# charge_drv.net
KiCad netlist of a schematic drawn in Altium Designer
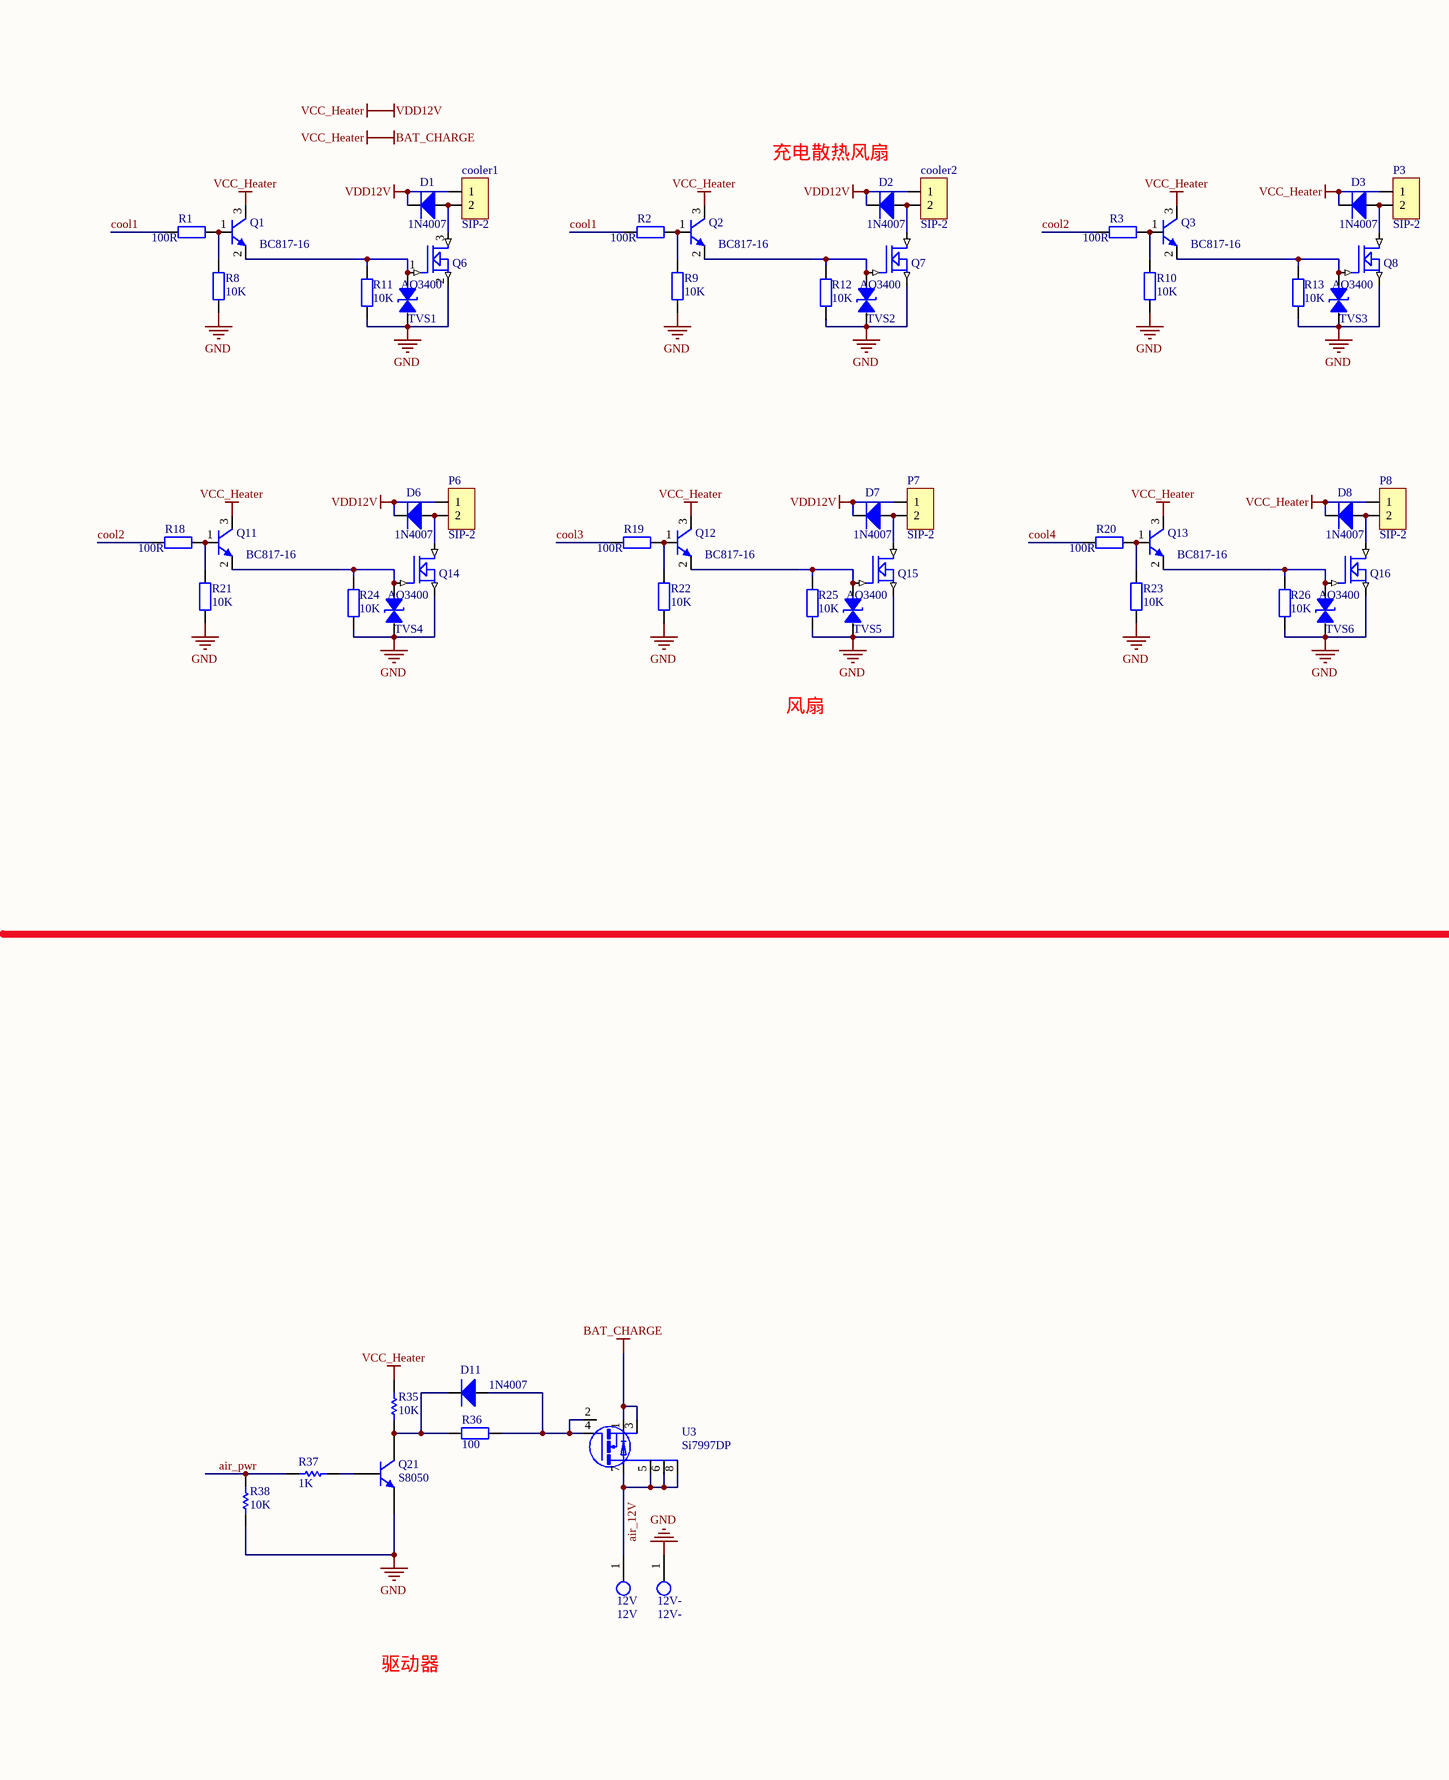
[diagram p0: charge_drv.SchDoc, left]
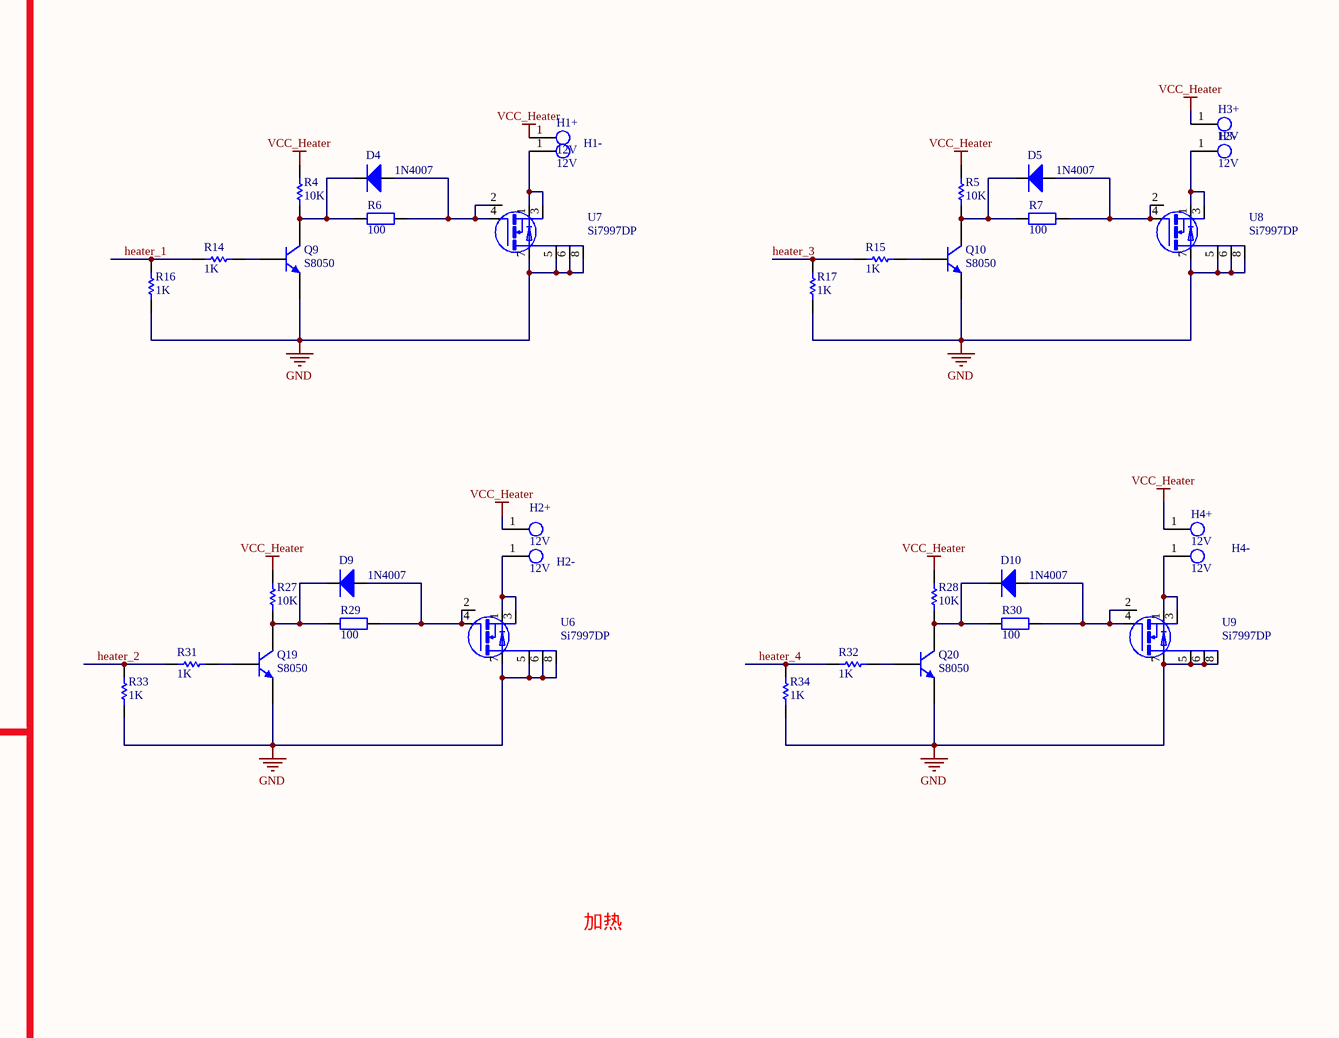
[diagram p1: charge_drv.SchDoc, right]

(export (version "E")
  (design (tool "Eeschema 10.0.6"))
  (components
    (comp (ref "12V") (value "12V") (footprint "FIX-4.5") (libsource (lib "Schlib_20110825") (part "TP")))
    (comp (ref "12V-") (value "12V-") (footprint "FIX-4.5") (libsource (lib "Schlib_20110825") (part "TP")))
    (comp (ref "cooler1")
      (value "SIP-2")
      (footprint "SIP-2A")
      (description "XH2.54 2P 立贴")
      (libsource (lib "XiaoyI") (part "SIP-2"))
    )
    (comp (ref "cooler2")
      (value "SIP-2")
      (footprint "SIP-2A")
      (description "XH2.54 2P 立贴")
      (libsource (lib "XiaoyI") (part "SIP-2"))
    )
    (comp (ref "D1")
      (value "1N4007")
      (footprint "DO-214-AC")
      (description "贴片二极管")
      (libsource (lib "XiaoyI") (part "DIODE2"))
    )
    (comp (ref "D2")
      (value "1N4007")
      (footprint "DO-214-AC")
      (description "贴片二极管")
      (libsource (lib "XiaoyI") (part "DIODE2"))
    )
    (comp (ref "D3")
      (value "1N4007")
      (footprint "DO-214-AC")
      (description "贴片二极管")
      (libsource (lib "XiaoyI") (part "DIODE2"))
    )
    (comp (ref "D4")
      (value "1N4007")
      (footprint "DO-214-AC")
      (description "贴片二极管")
      (libsource (lib "XiaoyI") (part "DIODE2"))
    )
    (comp (ref "D5")
      (value "1N4007")
      (footprint "DO-214-AC")
      (description "贴片二极管")
      (libsource (lib "XiaoyI") (part "DIODE2"))
    )
    (comp (ref "D6")
      (value "1N4007")
      (footprint "DO-214-AC")
      (description "贴片二极管")
      (libsource (lib "XiaoyI") (part "DIODE2"))
    )
    (comp (ref "D7")
      (value "1N4007")
      (footprint "DO-214-AC")
      (description "贴片二极管")
      (libsource (lib "XiaoyI") (part "DIODE2"))
    )
    (comp (ref "D8")
      (value "1N4007")
      (footprint "DO-214-AC")
      (description "贴片二极管")
      (libsource (lib "XiaoyI") (part "DIODE2"))
    )
    (comp (ref "D9")
      (value "1N4007")
      (footprint "DO-214-AC")
      (description "贴片二极管")
      (libsource (lib "XiaoyI") (part "DIODE2"))
    )
    (comp (ref "D10")
      (value "1N4007")
      (footprint "DO-214-AC")
      (description "贴片二极管")
      (libsource (lib "XiaoyI") (part "DIODE2"))
    )
    (comp (ref "D11")
      (value "1N4007")
      (footprint "DO-214-AC")
      (description "贴片二极管")
      (libsource (lib "XiaoyI") (part "DIODE2"))
    )
    (comp (ref "H1+") (value "12V") (footprint "FIX-4.5") (libsource (lib "Schlib_20110825") (part "TP")))
    (comp (ref "H1-") (value "12V") (footprint "FIX-4.5") (libsource (lib "Schlib_20110825") (part "TP")))
    (comp (ref "H2+") (value "12V") (footprint "FIX-4.5") (libsource (lib "Schlib_20110825") (part "TP")))
    (comp (ref "H2-") (value "12V") (footprint "FIX-4.5") (libsource (lib "Schlib_20110825") (part "TP")))
    (comp (ref "H3+") (value "12V") (footprint "FIX-4.5") (libsource (lib "Schlib_20110825") (part "TP")))
    (comp (ref "H3-") (value "12V") (footprint "FIX-4.5") (libsource (lib "Schlib_20110825") (part "TP")))
    (comp (ref "H4+") (value "12V") (footprint "FIX-4.5") (libsource (lib "Schlib_20110825") (part "TP")))
    (comp (ref "H4-") (value "12V") (footprint "FIX-4.5") (libsource (lib "Schlib_20110825") (part "TP")))
    (comp (ref "P3")
      (value "SIP-2")
      (footprint "SIP-2A")
      (description "XH2.54 2P 立贴")
      (libsource (lib "XiaoyI") (part "SIP-2"))
    )
    (comp (ref "P6")
      (value "SIP-2")
      (footprint "SIP-2A")
      (description "XH2.54 2P 立贴")
      (libsource (lib "XiaoyI") (part "SIP-2"))
    )
    (comp (ref "P7")
      (value "SIP-2")
      (footprint "SIP-2A")
      (description "XH2.54 2P 立贴")
      (libsource (lib "XiaoyI") (part "SIP-2"))
    )
    (comp (ref "P8")
      (value "SIP-2")
      (footprint "SIP-2A")
      (description "XH2.54 2P 立贴")
      (libsource (lib "XiaoyI") (part "SIP-2"))
    )
    (comp (ref "Q1")
      (value "BC817-16")
      (footprint "SOT23-3")
      (description "三极管")
      (libsource (lib "XiaoyI") (part "NPN-1"))
    )
    (comp (ref "Q2")
      (value "BC817-16")
      (footprint "SOT23-3")
      (description "三极管")
      (libsource (lib "XiaoyI") (part "NPN-1"))
    )
    (comp (ref "Q3")
      (value "BC817-16")
      (footprint "SOT23-3")
      (description "三极管")
      (libsource (lib "XiaoyI") (part "NPN-1"))
    )
    (comp (ref "Q6")
      (value "AO3400")
      (footprint "SOT23-3")
      (description "MOSFET N")
      (libsource (lib "XiaoyI") (part "MOSFET N"))
    )
    (comp (ref "Q7")
      (value "AO3400")
      (footprint "SOT23-3")
      (description "MOSFET N")
      (libsource (lib "") (part "MOSFET N_1"))
    )
    (comp (ref "Q8")
      (value "AO3400")
      (footprint "SOT23-3")
      (description "MOSFET N")
      (libsource (lib "") (part "MOSFET N_1"))
    )
    (comp (ref "Q9")
      (value "S8050")
      (footprint "SOT23-3")
      (description "NPN Bipolar Transistor")
      (fields (field (name "PUBLISHER") "Altium Limited"))
      (libsource (lib "Miscellaneous Devices") (part "NPN"))
    )
    (comp (ref "Q10")
      (value "S8050")
      (footprint "SOT23-3")
      (description "NPN Bipolar Transistor")
      (fields (field (name "PUBLISHER") "Altium Limited"))
      (libsource (lib "Miscellaneous Devices") (part "NPN"))
    )
    (comp (ref "Q11")
      (value "BC817-16")
      (footprint "SOT23-3")
      (description "三极管")
      (libsource (lib "XiaoyI") (part "NPN-1"))
    )
    (comp (ref "Q12")
      (value "BC817-16")
      (footprint "SOT23-3")
      (description "三极管")
      (libsource (lib "XiaoyI") (part "NPN-1"))
    )
    (comp (ref "Q13")
      (value "BC817-16")
      (footprint "SOT23-3")
      (description "三极管")
      (libsource (lib "XiaoyI") (part "NPN-1"))
    )
    (comp (ref "Q14")
      (value "AO3400")
      (footprint "SOT23-3")
      (description "MOSFET N")
      (libsource (lib "") (part "MOSFET N_1"))
    )
    (comp (ref "Q15")
      (value "AO3400")
      (footprint "SOT23-3")
      (description "MOSFET N")
      (libsource (lib "") (part "MOSFET N_1"))
    )
    (comp (ref "Q16")
      (value "AO3400")
      (footprint "SOT23-3")
      (description "MOSFET N")
      (libsource (lib "") (part "MOSFET N_1"))
    )
    (comp (ref "Q19")
      (value "S8050")
      (footprint "SOT23-3")
      (description "NPN Bipolar Transistor")
      (fields (field (name "PUBLISHER") "Altium Limited"))
      (libsource (lib "Miscellaneous Devices") (part "NPN"))
    )
    (comp (ref "Q20")
      (value "S8050")
      (footprint "SOT23-3")
      (description "NPN Bipolar Transistor")
      (fields (field (name "PUBLISHER") "Altium Limited"))
      (libsource (lib "Miscellaneous Devices") (part "NPN"))
    )
    (comp (ref "Q21")
      (value "S8050")
      (footprint "SOT23-3")
      (description "NPN Bipolar Transistor")
      (fields (field (name "PUBLISHER") "Altium Limited"))
      (libsource (lib "Miscellaneous Devices") (part "NPN"))
    )
    (comp (ref "R1")
      (value "100R")
      (footprint "0603R")
      (description "贴片电阻 5%")
      (libsource (lib "") (part "RES-SOP_3"))
    )
    (comp (ref "R2")
      (value "100R")
      (footprint "0603R")
      (description "贴片电阻 5%")
      (libsource (lib "") (part "RES-SOP_3"))
    )
    (comp (ref "R3")
      (value "100R")
      (footprint "0603R")
      (description "贴片电阻 5%")
      (libsource (lib "") (part "RES-SOP_3"))
    )
    (comp (ref "R4")
      (value "10K")
      (footprint "0603R")
      (description "Resistor")
      (fields (field (name "PUBLISHER") "Altium Limited"))
      (libsource (lib "Miscellaneous Devices") (part "Res1"))
    )
    (comp (ref "R5")
      (value "10K")
      (footprint "0603R")
      (description "Resistor")
      (fields (field (name "PUBLISHER") "Altium Limited"))
      (libsource (lib "Miscellaneous Devices") (part "Res1"))
    )
    (comp (ref "R6")
      (value "100")
      (footprint "0603R")
      (description "贴片电阻 5%")
      (libsource (lib "") (part "RES-SOP_1"))
    )
    (comp (ref "R7")
      (value "100")
      (footprint "0603R")
      (description "贴片电阻 5%")
      (libsource (lib "") (part "RES-SOP_1"))
    )
    (comp (ref "R8")
      (value "10K")
      (footprint "0603R")
      (description "贴片电阻 5%")
      (libsource (lib "") (part "RES-SOP_2"))
    )
    (comp (ref "R9")
      (value "10K")
      (footprint "0603R")
      (description "贴片电阻 5%")
      (libsource (lib "") (part "RES-SOP_2"))
    )
    (comp (ref "R10")
      (value "10K")
      (footprint "0603R")
      (description "贴片电阻 5%")
      (libsource (lib "") (part "RES-SOP_2"))
    )
    (comp (ref "R11")
      (value "10K")
      (footprint "0603R")
      (description "贴片电阻 5%")
      (libsource (lib "XiaoyI") (part "RES-SOP"))
    )
    (comp (ref "R12")
      (value "10K")
      (footprint "0603R")
      (description "贴片电阻 5%")
      (libsource (lib "XiaoyI") (part "RES-SOP"))
    )
    (comp (ref "R13")
      (value "10K")
      (footprint "0603R")
      (description "贴片电阻 5%")
      (libsource (lib "XiaoyI") (part "RES-SOP"))
    )
    (comp (ref "R14")
      (value "1K")
      (footprint "0603R")
      (description "Resistor")
      (fields (field (name "PUBLISHER") "Altium Limited"))
      (libsource (lib "Miscellaneous Devices") (part "Res1"))
    )
    (comp (ref "R15")
      (value "1K")
      (footprint "0603R")
      (description "Resistor")
      (fields (field (name "PUBLISHER") "Altium Limited"))
      (libsource (lib "Miscellaneous Devices") (part "Res1"))
    )
    (comp (ref "R16")
      (value "1K")
      (footprint "0603R")
      (description "Resistor")
      (fields (field (name "PUBLISHER") "Altium Limited"))
      (libsource (lib "Miscellaneous Devices") (part "Res1"))
    )
    (comp (ref "R17")
      (value "1K")
      (footprint "0603R")
      (description "Resistor")
      (fields (field (name "PUBLISHER") "Altium Limited"))
      (libsource (lib "Miscellaneous Devices") (part "Res1"))
    )
    (comp (ref "R18")
      (value "100R")
      (footprint "0603R")
      (description "贴片电阻 5%")
      (libsource (lib "") (part "RES-SOP_3"))
    )
    (comp (ref "R19")
      (value "100R")
      (footprint "0603R")
      (description "贴片电阻 5%")
      (libsource (lib "") (part "RES-SOP_3"))
    )
    (comp (ref "R20")
      (value "100R")
      (footprint "0603R")
      (description "贴片电阻 5%")
      (libsource (lib "") (part "RES-SOP_3"))
    )
    (comp (ref "R21")
      (value "10K")
      (footprint "0603R")
      (description "贴片电阻 5%")
      (libsource (lib "") (part "RES-SOP_2"))
    )
    (comp (ref "R22")
      (value "10K")
      (footprint "0603R")
      (description "贴片电阻 5%")
      (libsource (lib "") (part "RES-SOP_2"))
    )
    (comp (ref "R23")
      (value "10K")
      (footprint "0603R")
      (description "贴片电阻 5%")
      (libsource (lib "") (part "RES-SOP_2"))
    )
    (comp (ref "R24")
      (value "10K")
      (footprint "0603R")
      (description "贴片电阻 5%")
      (libsource (lib "XiaoyI") (part "RES-SOP"))
    )
    (comp (ref "R25")
      (value "10K")
      (footprint "0603R")
      (description "贴片电阻 5%")
      (libsource (lib "XiaoyI") (part "RES-SOP"))
    )
    (comp (ref "R26")
      (value "10K")
      (footprint "0603R")
      (description "贴片电阻 5%")
      (libsource (lib "XiaoyI") (part "RES-SOP"))
    )
    (comp (ref "R27")
      (value "10K")
      (footprint "0603R")
      (description "Resistor")
      (fields (field (name "PUBLISHER") "Altium Limited"))
      (libsource (lib "Miscellaneous Devices") (part "Res1"))
    )
    (comp (ref "R28")
      (value "10K")
      (footprint "0603R")
      (description "Resistor")
      (fields (field (name "PUBLISHER") "Altium Limited"))
      (libsource (lib "Miscellaneous Devices") (part "Res1"))
    )
    (comp (ref "R29")
      (value "100")
      (footprint "0603R")
      (description "贴片电阻 5%")
      (libsource (lib "") (part "RES-SOP_1"))
    )
    (comp (ref "R30")
      (value "100")
      (footprint "0603R")
      (description "贴片电阻 5%")
      (libsource (lib "") (part "RES-SOP_1"))
    )
    (comp (ref "R31")
      (value "1K")
      (footprint "0603R")
      (description "Resistor")
      (fields (field (name "PUBLISHER") "Altium Limited"))
      (libsource (lib "Miscellaneous Devices") (part "Res1"))
    )
    (comp (ref "R32")
      (value "1K")
      (footprint "0603R")
      (description "Resistor")
      (fields (field (name "PUBLISHER") "Altium Limited"))
      (libsource (lib "Miscellaneous Devices") (part "Res1"))
    )
    (comp (ref "R33")
      (value "1K")
      (footprint "0603R")
      (description "Resistor")
      (fields (field (name "PUBLISHER") "Altium Limited"))
      (libsource (lib "Miscellaneous Devices") (part "Res1"))
    )
    (comp (ref "R34")
      (value "1K")
      (footprint "0603R")
      (description "Resistor")
      (fields (field (name "PUBLISHER") "Altium Limited"))
      (libsource (lib "Miscellaneous Devices") (part "Res1"))
    )
    (comp (ref "R35")
      (value "10K")
      (footprint "0603R")
      (description "Resistor")
      (fields (field (name "PUBLISHER") "Altium Limited"))
      (libsource (lib "Miscellaneous Devices") (part "Res1"))
    )
    (comp (ref "R36")
      (value "100")
      (footprint "0603R")
      (description "贴片电阻 5%")
      (libsource (lib "") (part "RES-SOP_1"))
    )
    (comp (ref "R37")
      (value "1K")
      (footprint "0603R")
      (description "Resistor")
      (fields (field (name "PUBLISHER") "Altium Limited"))
      (libsource (lib "Miscellaneous Devices") (part "Res1"))
    )
    (comp (ref "R38")
      (value "10K")
      (footprint "0603R")
      (description "Resistor")
      (fields (field (name "PUBLISHER") "Altium Limited"))
      (libsource (lib "Miscellaneous Devices") (part "Res1"))
    )
    (comp (ref "TVS1")
      (value "ESD5Z5.0CT1G")
      (footprint "SOD-523")
      (description "TVS")
      (libsource (lib "XiaoyI") (part "TVS-1"))
    )
    (comp (ref "TVS2")
      (value "ESD5Z5.0CT1G")
      (footprint "SOD-523")
      (description "TVS")
      (libsource (lib "XiaoyI") (part "TVS-1"))
    )
    (comp (ref "TVS3")
      (value "ESD5Z5.0CT1G")
      (footprint "SOD-523")
      (description "TVS")
      (libsource (lib "XiaoyI") (part "TVS-1"))
    )
    (comp (ref "TVS4")
      (value "ESD5Z5.0CT1G")
      (footprint "SOD-523")
      (description "TVS")
      (libsource (lib "XiaoyI") (part "TVS-1"))
    )
    (comp (ref "TVS5")
      (value "ESD5Z5.0CT1G")
      (footprint "SOD-523")
      (description "TVS")
      (libsource (lib "XiaoyI") (part "TVS-1"))
    )
    (comp (ref "TVS6")
      (value "ESD5Z5.0CT1G")
      (footprint "SOD-523")
      (description "TVS")
      (libsource (lib "XiaoyI") (part "TVS-1"))
    )
    (comp (ref "U3")
      (value "Si7997DP")
      (footprint "PowerPAK SO-8")
      (description "Sia430DJ")
      (libsource (lib "Schlib_20110825") (part "Si7997DP"))
    )
    (comp (ref "U6")
      (value "Si7997DP")
      (footprint "PowerPAK SO-8")
      (description "Sia430DJ")
      (libsource (lib "Schlib_20110825") (part "Si7997DP"))
    )
    (comp (ref "U7")
      (value "Si7997DP")
      (footprint "PowerPAK SO-8")
      (description "Sia430DJ")
      (libsource (lib "Schlib_20110825") (part "Si7997DP"))
    )
    (comp (ref "U8")
      (value "Si7997DP")
      (footprint "PowerPAK SO-8")
      (description "Sia430DJ")
      (libsource (lib "Schlib_20110825") (part "Si7997DP"))
    )
    (comp (ref "U9")
      (value "Si7997DP")
      (footprint "PowerPAK SO-8")
      (description "Sia430DJ")
      (libsource (lib "Schlib_20110825") (part "Si7997DP"))
    )
  )
  (nets
    (net (code "1") (name "/air_12V") (class "Default")
      (node (ref "12V") (pin "1") (pintype "passive"))
      (node (ref "U3") (pin "5") (pinfunction "D_5") (pintype "passive"))
      (node (ref "U3") (pin "6") (pinfunction "D_6") (pintype "passive"))
      (node (ref "U3") (pin "7") (pinfunction "D_7") (pintype "passive"))
      (node (ref "U3") (pin "8") (pinfunction "D_8") (pintype "passive"))
    )
    (net (code "2") (name "/air_pwr") (class "Default")
      (node (ref "R37") (pin "2") (pinfunction "2_2") (pintype "passive"))
      (node (ref "R38") (pin "1") (pinfunction "1_1") (pintype "passive"))
    )
    (net (code "3") (name "/cool1") (class "Default")
      (node (ref "R1") (pin "2") (pinfunction "2_2") (pintype "passive"))
      (node (ref "R2") (pin "2") (pinfunction "2_2") (pintype "passive"))
    )
    (net (code "4") (name "/cool2") (class "Default")
      (node (ref "R18") (pin "2") (pinfunction "2_2") (pintype "passive"))
      (node (ref "R3") (pin "2") (pinfunction "2_2") (pintype "passive"))
    )
    (net (code "5") (name "/cool3") (class "Default")
      (node (ref "R19") (pin "2") (pinfunction "2_2") (pintype "passive"))
    )
    (net (code "6") (name "/cool4") (class "Default")
      (node (ref "R20") (pin "2") (pinfunction "2_2") (pintype "passive"))
    )
    (net (code "7") (name "/heater_1") (class "Default")
      (node (ref "R14") (pin "2") (pinfunction "2_2") (pintype "passive"))
      (node (ref "R16") (pin "1") (pinfunction "1_1") (pintype "passive"))
    )
    (net (code "8") (name "/heater_2") (class "Default")
      (node (ref "R31") (pin "2") (pinfunction "2_2") (pintype "passive"))
      (node (ref "R33") (pin "1") (pinfunction "1_1") (pintype "passive"))
    )
    (net (code "9") (name "/heater_3") (class "Default")
      (node (ref "R15") (pin "2") (pinfunction "2_2") (pintype "passive"))
      (node (ref "R17") (pin "1") (pinfunction "1_1") (pintype "passive"))
    )
    (net (code "10") (name "/heater_4") (class "Default")
      (node (ref "R32") (pin "2") (pinfunction "2_2") (pintype "passive"))
      (node (ref "R34") (pin "1") (pinfunction "1_1") (pintype "passive"))
    )
    (net (code "11") (name "BAT_CHARGE") (class "Default")
      (node (ref "D1") (pin "2") (pinfunction "K_2") (pintype "passive"))
      (node (ref "D2") (pin "2") (pinfunction "K_2") (pintype "passive"))
      (node (ref "D3") (pin "2") (pinfunction "K_2") (pintype "passive"))
      (node (ref "D6") (pin "2") (pinfunction "K_2") (pintype "passive"))
      (node (ref "D7") (pin "2") (pinfunction "K_2") (pintype "passive"))
      (node (ref "D8") (pin "2") (pinfunction "K_2") (pintype "passive"))
      (node (ref "H1+") (pin "1") (pintype "passive"))
      (node (ref "H2+") (pin "1") (pintype "passive"))
      (node (ref "H3+") (pin "1") (pintype "passive"))
      (node (ref "H4+") (pin "1") (pintype "passive"))
      (node (ref "P3") (pin "1") (pinfunction "1_1") (pintype "passive"))
      (node (ref "P6") (pin "1") (pinfunction "1_1") (pintype "passive"))
      (node (ref "P7") (pin "1") (pinfunction "1_1") (pintype "passive"))
      (node (ref "P8") (pin "1") (pinfunction "1_1") (pintype "passive"))
      (node (ref "Q1") (pin "3") (pinfunction "C_3") (pintype "passive"))
      (node (ref "Q11") (pin "3") (pinfunction "C_3") (pintype "passive"))
      (node (ref "Q12") (pin "3") (pinfunction "C_3") (pintype "passive"))
      (node (ref "Q13") (pin "3") (pinfunction "C_3") (pintype "passive"))
      (node (ref "Q2") (pin "3") (pinfunction "C_3") (pintype "passive"))
      (node (ref "Q3") (pin "3") (pinfunction "C_3") (pintype "passive"))
      (node (ref "R27") (pin "2") (pinfunction "2_2") (pintype "passive"))
      (node (ref "R28") (pin "2") (pinfunction "2_2") (pintype "passive"))
      (node (ref "R35") (pin "2") (pinfunction "2_2") (pintype "passive"))
      (node (ref "R4") (pin "2") (pinfunction "2_2") (pintype "passive"))
      (node (ref "R5") (pin "2") (pinfunction "2_2") (pintype "passive"))
      (node (ref "U3") (pin "1") (pinfunction "S_1") (pintype "passive"))
      (node (ref "U3") (pin "3") (pinfunction "S_3") (pintype "passive"))
      (node (ref "cooler1") (pin "1") (pinfunction "1_1") (pintype "passive"))
      (node (ref "cooler2") (pin "1") (pinfunction "1_1") (pintype "passive"))
    )
    (net (code "12") (name "GND") (class "Default")
      (node (ref "12V-") (pin "1") (pintype "passive"))
      (node (ref "Q10") (pin "2") (pinfunction "E_2") (pintype "passive"))
      (node (ref "Q14") (pin "2") (pinfunction "S_2") (pintype "output"))
      (node (ref "Q15") (pin "2") (pinfunction "S_2") (pintype "output"))
      (node (ref "Q16") (pin "2") (pinfunction "S_2") (pintype "output"))
      (node (ref "Q19") (pin "2") (pinfunction "E_2") (pintype "passive"))
      (node (ref "Q20") (pin "2") (pinfunction "E_2") (pintype "passive"))
      (node (ref "Q21") (pin "2") (pinfunction "E_2") (pintype "passive"))
      (node (ref "Q6") (pin "2") (pinfunction "S_2") (pintype "output"))
      (node (ref "Q7") (pin "2") (pinfunction "S_2") (pintype "output"))
      (node (ref "Q8") (pin "2") (pinfunction "S_2") (pintype "output"))
      (node (ref "Q9") (pin "2") (pinfunction "E_2") (pintype "passive"))
      (node (ref "R10") (pin "1") (pinfunction "1_1") (pintype "passive"))
      (node (ref "R11") (pin "2") (pinfunction "2_2") (pintype "passive"))
      (node (ref "R12") (pin "2") (pinfunction "2_2") (pintype "passive"))
      (node (ref "R13") (pin "2") (pinfunction "2_2") (pintype "passive"))
      (node (ref "R16") (pin "2") (pinfunction "2_2") (pintype "passive"))
      (node (ref "R17") (pin "2") (pinfunction "2_2") (pintype "passive"))
      (node (ref "R21") (pin "1") (pinfunction "1_1") (pintype "passive"))
      (node (ref "R22") (pin "1") (pinfunction "1_1") (pintype "passive"))
      (node (ref "R23") (pin "1") (pinfunction "1_1") (pintype "passive"))
      (node (ref "R24") (pin "2") (pinfunction "2_2") (pintype "passive"))
      (node (ref "R25") (pin "2") (pinfunction "2_2") (pintype "passive"))
      (node (ref "R26") (pin "2") (pinfunction "2_2") (pintype "passive"))
      (node (ref "R33") (pin "2") (pinfunction "2_2") (pintype "passive"))
      (node (ref "R34") (pin "2") (pinfunction "2_2") (pintype "passive"))
      (node (ref "R38") (pin "2") (pinfunction "2_2") (pintype "passive"))
      (node (ref "R8") (pin "1") (pinfunction "1_1") (pintype "passive"))
      (node (ref "R9") (pin "1") (pinfunction "1_1") (pintype "passive"))
      (node (ref "TVS1") (pin "1") (pinfunction "A_1") (pintype "passive"))
      (node (ref "TVS2") (pin "1") (pinfunction "A_1") (pintype "passive"))
      (node (ref "TVS3") (pin "1") (pinfunction "A_1") (pintype "passive"))
      (node (ref "TVS4") (pin "1") (pinfunction "A_1") (pintype "passive"))
      (node (ref "TVS5") (pin "1") (pinfunction "A_1") (pintype "passive"))
      (node (ref "TVS6") (pin "1") (pinfunction "A_1") (pintype "passive"))
      (node (ref "U6") (pin "5") (pinfunction "D_5") (pintype "passive"))
      (node (ref "U6") (pin "6") (pinfunction "D_6") (pintype "passive"))
      (node (ref "U6") (pin "7") (pinfunction "D_7") (pintype "passive"))
      (node (ref "U6") (pin "8") (pinfunction "D_8") (pintype "passive"))
      (node (ref "U7") (pin "5") (pinfunction "D_5") (pintype "passive"))
      (node (ref "U7") (pin "6") (pinfunction "D_6") (pintype "passive"))
      (node (ref "U7") (pin "7") (pinfunction "D_7") (pintype "passive"))
      (node (ref "U7") (pin "8") (pinfunction "D_8") (pintype "passive"))
      (node (ref "U8") (pin "5") (pinfunction "D_5") (pintype "passive"))
      (node (ref "U8") (pin "6") (pinfunction "D_6") (pintype "passive"))
      (node (ref "U8") (pin "7") (pinfunction "D_7") (pintype "passive"))
      (node (ref "U8") (pin "8") (pinfunction "D_8") (pintype "passive"))
      (node (ref "U9") (pin "5") (pinfunction "D_5") (pintype "passive"))
      (node (ref "U9") (pin "6") (pinfunction "D_6") (pintype "passive"))
      (node (ref "U9") (pin "7") (pinfunction "D_7") (pintype "passive"))
      (node (ref "U9") (pin "8") (pinfunction "D_8") (pintype "passive"))
    )
    (net (code "13") (name "Net-(D1-A)") (class "Default")
      (node (ref "D1") (pin "1") (pinfunction "A_1") (pintype "passive"))
      (node (ref "Q6") (pin "3") (pinfunction "D_3") (pintype "input"))
      (node (ref "cooler1") (pin "2") (pinfunction "2_2") (pintype "passive"))
    )
    (net (code "14") (name "Net-(D2-A)") (class "Default")
      (node (ref "D2") (pin "1") (pinfunction "A_1") (pintype "passive"))
      (node (ref "Q7") (pin "3") (pinfunction "D_3") (pintype "input"))
      (node (ref "cooler2") (pin "2") (pinfunction "2_2") (pintype "passive"))
    )
    (net (code "15") (name "Net-(D3-A)") (class "Default")
      (node (ref "D3") (pin "1") (pinfunction "A_1") (pintype "passive"))
      (node (ref "P3") (pin "2") (pinfunction "2_2") (pintype "passive"))
      (node (ref "Q8") (pin "3") (pinfunction "D_3") (pintype "input"))
    )
    (net (code "16") (name "Net-(D4-A)") (class "Default")
      (node (ref "D4") (pin "1") (pinfunction "A_1") (pintype "passive"))
      (node (ref "R6") (pin "2") (pinfunction "2_2") (pintype "passive"))
      (node (ref "U7") (pin "2") (pinfunction "G_2") (pintype "passive"))
      (node (ref "U7") (pin "4") (pinfunction "G_4") (pintype "passive"))
    )
    (net (code "17") (name "Net-(D4-K)") (class "Default")
      (node (ref "D4") (pin "2") (pinfunction "K_2") (pintype "passive"))
      (node (ref "Q9") (pin "3") (pinfunction "C_3") (pintype "passive"))
      (node (ref "R4") (pin "1") (pinfunction "1_1") (pintype "passive"))
      (node (ref "R6") (pin "1") (pinfunction "1_1") (pintype "passive"))
    )
    (net (code "18") (name "Net-(D5-A)") (class "Default")
      (node (ref "D5") (pin "1") (pinfunction "A_1") (pintype "passive"))
      (node (ref "R7") (pin "2") (pinfunction "2_2") (pintype "passive"))
      (node (ref "U8") (pin "2") (pinfunction "G_2") (pintype "passive"))
      (node (ref "U8") (pin "4") (pinfunction "G_4") (pintype "passive"))
    )
    (net (code "19") (name "Net-(D5-K)") (class "Default")
      (node (ref "D5") (pin "2") (pinfunction "K_2") (pintype "passive"))
      (node (ref "Q10") (pin "3") (pinfunction "C_3") (pintype "passive"))
      (node (ref "R5") (pin "1") (pinfunction "1_1") (pintype "passive"))
      (node (ref "R7") (pin "1") (pinfunction "1_1") (pintype "passive"))
    )
    (net (code "20") (name "Net-(D6-A)") (class "Default")
      (node (ref "D6") (pin "1") (pinfunction "A_1") (pintype "passive"))
      (node (ref "P6") (pin "2") (pinfunction "2_2") (pintype "passive"))
      (node (ref "Q14") (pin "3") (pinfunction "D_3") (pintype "input"))
    )
    (net (code "21") (name "Net-(D7-A)") (class "Default")
      (node (ref "D7") (pin "1") (pinfunction "A_1") (pintype "passive"))
      (node (ref "P7") (pin "2") (pinfunction "2_2") (pintype "passive"))
      (node (ref "Q15") (pin "3") (pinfunction "D_3") (pintype "input"))
    )
    (net (code "22") (name "Net-(D8-A)") (class "Default")
      (node (ref "D8") (pin "1") (pinfunction "A_1") (pintype "passive"))
      (node (ref "P8") (pin "2") (pinfunction "2_2") (pintype "passive"))
      (node (ref "Q16") (pin "3") (pinfunction "D_3") (pintype "input"))
    )
    (net (code "23") (name "Net-(D9-A)") (class "Default")
      (node (ref "D9") (pin "1") (pinfunction "A_1") (pintype "passive"))
      (node (ref "R29") (pin "2") (pinfunction "2_2") (pintype "passive"))
      (node (ref "U6") (pin "2") (pinfunction "G_2") (pintype "passive"))
      (node (ref "U6") (pin "4") (pinfunction "G_4") (pintype "passive"))
    )
    (net (code "24") (name "Net-(D9-K)") (class "Default")
      (node (ref "D9") (pin "2") (pinfunction "K_2") (pintype "passive"))
      (node (ref "Q19") (pin "3") (pinfunction "C_3") (pintype "passive"))
      (node (ref "R27") (pin "1") (pinfunction "1_1") (pintype "passive"))
      (node (ref "R29") (pin "1") (pinfunction "1_1") (pintype "passive"))
    )
    (net (code "25") (name "Net-(D10-A)") (class "Default")
      (node (ref "D10") (pin "1") (pinfunction "A_1") (pintype "passive"))
      (node (ref "R30") (pin "2") (pinfunction "2_2") (pintype "passive"))
      (node (ref "U9") (pin "2") (pinfunction "G_2") (pintype "passive"))
      (node (ref "U9") (pin "4") (pinfunction "G_4") (pintype "passive"))
    )
    (net (code "26") (name "Net-(D10-K)") (class "Default")
      (node (ref "D10") (pin "2") (pinfunction "K_2") (pintype "passive"))
      (node (ref "Q20") (pin "3") (pinfunction "C_3") (pintype "passive"))
      (node (ref "R28") (pin "1") (pinfunction "1_1") (pintype "passive"))
      (node (ref "R30") (pin "1") (pinfunction "1_1") (pintype "passive"))
    )
    (net (code "27") (name "Net-(D11-A)") (class "Default")
      (node (ref "D11") (pin "1") (pinfunction "A_1") (pintype "passive"))
      (node (ref "R36") (pin "2") (pinfunction "2_2") (pintype "passive"))
      (node (ref "U3") (pin "2") (pinfunction "G_2") (pintype "passive"))
      (node (ref "U3") (pin "4") (pinfunction "G_4") (pintype "passive"))
    )
    (net (code "28") (name "Net-(D11-K)") (class "Default")
      (node (ref "D11") (pin "2") (pinfunction "K_2") (pintype "passive"))
      (node (ref "Q21") (pin "3") (pinfunction "C_3") (pintype "passive"))
      (node (ref "R35") (pin "1") (pinfunction "1_1") (pintype "passive"))
      (node (ref "R36") (pin "1") (pinfunction "1_1") (pintype "passive"))
    )
    (net (code "29") (name "Net-(H1--Pad1)") (class "Default")
      (node (ref "H1-") (pin "1") (pintype "passive"))
      (node (ref "U7") (pin "1") (pinfunction "S_1") (pintype "passive"))
      (node (ref "U7") (pin "3") (pinfunction "S_3") (pintype "passive"))
    )
    (net (code "30") (name "Net-(H2--Pad1)") (class "Default")
      (node (ref "H2-") (pin "1") (pintype "passive"))
      (node (ref "U6") (pin "1") (pinfunction "S_1") (pintype "passive"))
      (node (ref "U6") (pin "3") (pinfunction "S_3") (pintype "passive"))
    )
    (net (code "31") (name "Net-(H3--Pad1)") (class "Default")
      (node (ref "H3-") (pin "1") (pintype "passive"))
      (node (ref "U8") (pin "1") (pinfunction "S_1") (pintype "passive"))
      (node (ref "U8") (pin "3") (pinfunction "S_3") (pintype "passive"))
    )
    (net (code "32") (name "Net-(H4--Pad1)") (class "Default")
      (node (ref "H4-") (pin "1") (pintype "passive"))
      (node (ref "U9") (pin "1") (pinfunction "S_1") (pintype "passive"))
      (node (ref "U9") (pin "3") (pinfunction "S_3") (pintype "passive"))
    )
    (net (code "33") (name "Net-(Q1-B)") (class "Default")
      (node (ref "Q1") (pin "1") (pinfunction "B_1") (pintype "passive"))
      (node (ref "R1") (pin "1") (pinfunction "1_1") (pintype "passive"))
      (node (ref "R8") (pin "2") (pinfunction "2_2") (pintype "passive"))
    )
    (net (code "34") (name "Net-(Q1-E)") (class "Default")
      (node (ref "Q1") (pin "2") (pinfunction "E_2") (pintype "passive"))
      (node (ref "Q6") (pin "1") (pinfunction "G_1") (pintype "input"))
      (node (ref "R11") (pin "1") (pinfunction "1_1") (pintype "passive"))
      (node (ref "TVS1") (pin "2") (pinfunction "B_2") (pintype "passive"))
    )
    (net (code "35") (name "Net-(Q2-B)") (class "Default")
      (node (ref "Q2") (pin "1") (pinfunction "B_1") (pintype "passive"))
      (node (ref "R2") (pin "1") (pinfunction "1_1") (pintype "passive"))
      (node (ref "R9") (pin "2") (pinfunction "2_2") (pintype "passive"))
    )
    (net (code "36") (name "Net-(Q2-E)") (class "Default")
      (node (ref "Q2") (pin "2") (pinfunction "E_2") (pintype "passive"))
      (node (ref "Q7") (pin "1") (pinfunction "G_1") (pintype "input"))
      (node (ref "R12") (pin "1") (pinfunction "1_1") (pintype "passive"))
      (node (ref "TVS2") (pin "2") (pinfunction "B_2") (pintype "passive"))
    )
    (net (code "37") (name "Net-(Q3-B)") (class "Default")
      (node (ref "Q3") (pin "1") (pinfunction "B_1") (pintype "passive"))
      (node (ref "R10") (pin "2") (pinfunction "2_2") (pintype "passive"))
      (node (ref "R3") (pin "1") (pinfunction "1_1") (pintype "passive"))
    )
    (net (code "38") (name "Net-(Q3-E)") (class "Default")
      (node (ref "Q3") (pin "2") (pinfunction "E_2") (pintype "passive"))
      (node (ref "Q8") (pin "1") (pinfunction "G_1") (pintype "input"))
      (node (ref "R13") (pin "1") (pinfunction "1_1") (pintype "passive"))
      (node (ref "TVS3") (pin "2") (pinfunction "B_2") (pintype "passive"))
    )
    (net (code "39") (name "Net-(Q9-B)") (class "Default")
      (node (ref "Q9") (pin "1") (pinfunction "B_1") (pintype "passive"))
      (node (ref "R14") (pin "1") (pinfunction "1_1") (pintype "passive"))
    )
    (net (code "40") (name "Net-(Q10-B)") (class "Default")
      (node (ref "Q10") (pin "1") (pinfunction "B_1") (pintype "passive"))
      (node (ref "R15") (pin "1") (pinfunction "1_1") (pintype "passive"))
    )
    (net (code "41") (name "Net-(Q11-B)") (class "Default")
      (node (ref "Q11") (pin "1") (pinfunction "B_1") (pintype "passive"))
      (node (ref "R18") (pin "1") (pinfunction "1_1") (pintype "passive"))
      (node (ref "R21") (pin "2") (pinfunction "2_2") (pintype "passive"))
    )
    (net (code "42") (name "Net-(Q11-E)") (class "Default")
      (node (ref "Q11") (pin "2") (pinfunction "E_2") (pintype "passive"))
      (node (ref "Q14") (pin "1") (pinfunction "G_1") (pintype "input"))
      (node (ref "R24") (pin "1") (pinfunction "1_1") (pintype "passive"))
      (node (ref "TVS4") (pin "2") (pinfunction "B_2") (pintype "passive"))
    )
    (net (code "43") (name "Net-(Q12-B)") (class "Default")
      (node (ref "Q12") (pin "1") (pinfunction "B_1") (pintype "passive"))
      (node (ref "R19") (pin "1") (pinfunction "1_1") (pintype "passive"))
      (node (ref "R22") (pin "2") (pinfunction "2_2") (pintype "passive"))
    )
    (net (code "44") (name "Net-(Q12-E)") (class "Default")
      (node (ref "Q12") (pin "2") (pinfunction "E_2") (pintype "passive"))
      (node (ref "Q15") (pin "1") (pinfunction "G_1") (pintype "input"))
      (node (ref "R25") (pin "1") (pinfunction "1_1") (pintype "passive"))
      (node (ref "TVS5") (pin "2") (pinfunction "B_2") (pintype "passive"))
    )
    (net (code "45") (name "Net-(Q13-B)") (class "Default")
      (node (ref "Q13") (pin "1") (pinfunction "B_1") (pintype "passive"))
      (node (ref "R20") (pin "1") (pinfunction "1_1") (pintype "passive"))
      (node (ref "R23") (pin "2") (pinfunction "2_2") (pintype "passive"))
    )
    (net (code "46") (name "Net-(Q13-E)") (class "Default")
      (node (ref "Q13") (pin "2") (pinfunction "E_2") (pintype "passive"))
      (node (ref "Q16") (pin "1") (pinfunction "G_1") (pintype "input"))
      (node (ref "R26") (pin "1") (pinfunction "1_1") (pintype "passive"))
      (node (ref "TVS6") (pin "2") (pinfunction "B_2") (pintype "passive"))
    )
    (net (code "47") (name "Net-(Q19-B)") (class "Default")
      (node (ref "Q19") (pin "1") (pinfunction "B_1") (pintype "passive"))
      (node (ref "R31") (pin "1") (pinfunction "1_1") (pintype "passive"))
    )
    (net (code "48") (name "Net-(Q20-B)") (class "Default")
      (node (ref "Q20") (pin "1") (pinfunction "B_1") (pintype "passive"))
      (node (ref "R32") (pin "1") (pinfunction "1_1") (pintype "passive"))
    )
    (net (code "49") (name "Net-(Q21-B)") (class "Default")
      (node (ref "Q21") (pin "1") (pinfunction "B_1") (pintype "passive"))
      (node (ref "R37") (pin "1") (pinfunction "1_1") (pintype "passive"))
    )
  )
)
